# RLC_renonant.net
KiCad netlist of a schematic drawn in Altium Designer
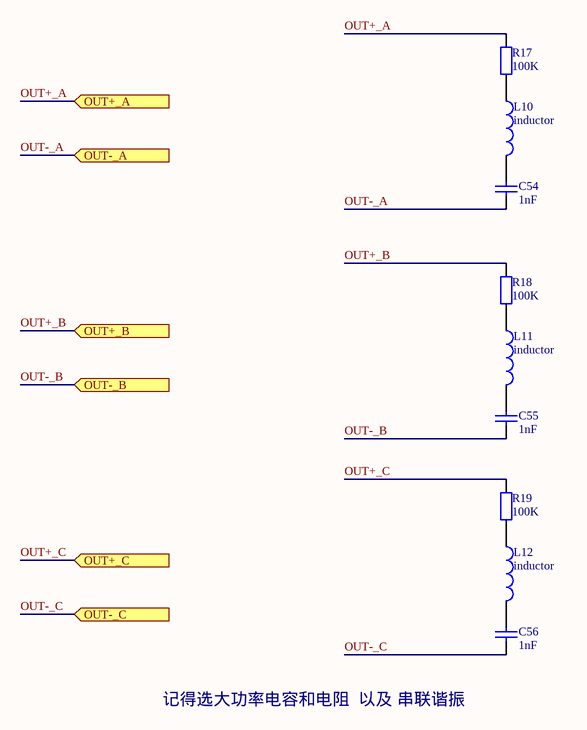
[diagram p0: RLC_renonant.SchDoc]

(export (version "E")
  (design (tool "Eeschema 10.0.6"))
  (components
    (comp (ref "C54") (value "1nF") (footprint "RAD-0.2") (libsource (lib "MyLibrary") (part "Cap")))
    (comp (ref "C55") (value "1nF") (footprint "RAD-0.2") (libsource (lib "MyLibrary") (part "Cap")))
    (comp (ref "C56") (value "1nF") (footprint "RAD-0.2") (libsource (lib "MyLibrary") (part "Cap")))
    (comp (ref "L10") (value "inductor") (footprint "inductor") (libsource (lib "Dugu") (part "inductor")))
    (comp (ref "L11") (value "inductor") (footprint "inductor") (libsource (lib "Dugu") (part "inductor")))
    (comp (ref "L12") (value "inductor") (footprint "inductor") (libsource (lib "Dugu") (part "inductor")))
    (comp (ref "R17")
      (value "100K")
      (footprint "Res_big")
      (fields
        (field (name "Comment") "Res")
        (field (name "原理图绘制者") "刘永钦")
        (field (name "原理图提供者") "刘永钦")
        (field (name "原理图审核人1") "徐鹏飞")
        (field (name "封装0805绘制者") "刘永钦")
        (field (name "封装0805提供者") "刘永钦")
        (field (name "封装0805审核人1") "徐鹏飞")
        (field (name "原理图审核人2") "朱觉文")
        (field (name "封装0805审核人2") "朱觉文")
        (field (name "封装0603提供者") "刘永钦")
        (field (name "封装0603审核人2") "朱觉文")
        (field (name "封装0603审核人1") "徐鹏飞")
        (field (name "封装2512-RESC6332X06N审核人2") "朱觉文")
        (field (name "封装2512-RESC6332X06N提供者") "刘永钦")
        (field (name "封装2512-RESC6332X06N审核人1") "徐鹏飞")
        (field (name "封装0603绘制者") "刘永钦")
        (field (name "封装2512-RESC6332X06N绘制者") "刘永钦")
      )
      (libsource (lib "DuGu") (part "Res"))
    )
    (comp (ref "R18")
      (value "100K")
      (footprint "Res_big")
      (fields
        (field (name "Comment") "Res")
        (field (name "原理图绘制者") "刘永钦")
        (field (name "原理图提供者") "刘永钦")
        (field (name "原理图审核人1") "徐鹏飞")
        (field (name "封装0805绘制者") "刘永钦")
        (field (name "封装0805提供者") "刘永钦")
        (field (name "封装0805审核人1") "徐鹏飞")
        (field (name "原理图审核人2") "朱觉文")
        (field (name "封装0805审核人2") "朱觉文")
        (field (name "封装0603提供者") "刘永钦")
        (field (name "封装0603审核人2") "朱觉文")
        (field (name "封装0603审核人1") "徐鹏飞")
        (field (name "封装2512-RESC6332X06N审核人2") "朱觉文")
        (field (name "封装2512-RESC6332X06N提供者") "刘永钦")
        (field (name "封装2512-RESC6332X06N审核人1") "徐鹏飞")
        (field (name "封装0603绘制者") "刘永钦")
        (field (name "封装2512-RESC6332X06N绘制者") "刘永钦")
      )
      (libsource (lib "DuGu") (part "Res"))
    )
    (comp (ref "R19")
      (value "100K")
      (footprint "Res_big")
      (fields
        (field (name "Comment") "Res")
        (field (name "原理图绘制者") "刘永钦")
        (field (name "原理图提供者") "刘永钦")
        (field (name "原理图审核人1") "徐鹏飞")
        (field (name "封装0805绘制者") "刘永钦")
        (field (name "封装0805提供者") "刘永钦")
        (field (name "封装0805审核人1") "徐鹏飞")
        (field (name "原理图审核人2") "朱觉文")
        (field (name "封装0805审核人2") "朱觉文")
        (field (name "封装0603提供者") "刘永钦")
        (field (name "封装0603审核人2") "朱觉文")
        (field (name "封装0603审核人1") "徐鹏飞")
        (field (name "封装2512-RESC6332X06N审核人2") "朱觉文")
        (field (name "封装2512-RESC6332X06N提供者") "刘永钦")
        (field (name "封装2512-RESC6332X06N审核人1") "徐鹏飞")
        (field (name "封装0603绘制者") "刘永钦")
        (field (name "封装2512-RESC6332X06N绘制者") "刘永钦")
      )
      (libsource (lib "DuGu") (part "Res"))
    )
  )
  (nets
    (net (code "1") (name "/OUT+_A") (class "Default")
      (node (ref "R17") (pin "1") (pinfunction "1_1") (pintype "passive"))
    )
    (net (code "2") (name "/OUT+_B") (class "Default")
      (node (ref "R18") (pin "1") (pinfunction "1_1") (pintype "passive"))
    )
    (net (code "3") (name "/OUT+_C") (class "Default")
      (node (ref "R19") (pin "1") (pinfunction "1_1") (pintype "passive"))
    )
    (net (code "4") (name "/OUT-_A") (class "Default")
      (node (ref "C54") (pin "1") (pinfunction "1_1") (pintype "passive"))
    )
    (net (code "5") (name "/OUT-_B") (class "Default")
      (node (ref "C55") (pin "1") (pinfunction "1_1") (pintype "passive"))
    )
    (net (code "6") (name "/OUT-_C") (class "Default")
      (node (ref "C56") (pin "1") (pinfunction "1_1") (pintype "passive"))
    )
    (net (code "7") (name "Net-(C54-Pad2)") (class "Default")
      (node (ref "C54") (pin "2") (pinfunction "2_2") (pintype "passive"))
      (node (ref "L10") (pin "2") (pinfunction "2_2") (pintype "passive"))
    )
    (net (code "8") (name "Net-(C55-Pad2)") (class "Default")
      (node (ref "C55") (pin "2") (pinfunction "2_2") (pintype "passive"))
      (node (ref "L11") (pin "2") (pinfunction "2_2") (pintype "passive"))
    )
    (net (code "9") (name "Net-(C56-Pad2)") (class "Default")
      (node (ref "C56") (pin "2") (pinfunction "2_2") (pintype "passive"))
      (node (ref "L12") (pin "2") (pinfunction "2_2") (pintype "passive"))
    )
    (net (code "10") (name "Net-(L10-Pad1)") (class "Default")
      (node (ref "L10") (pin "1") (pinfunction "1_1") (pintype "passive"))
      (node (ref "R17") (pin "2") (pinfunction "2_2") (pintype "passive"))
    )
    (net (code "11") (name "Net-(L11-Pad1)") (class "Default")
      (node (ref "L11") (pin "1") (pinfunction "1_1") (pintype "passive"))
      (node (ref "R18") (pin "2") (pinfunction "2_2") (pintype "passive"))
    )
    (net (code "12") (name "Net-(L12-Pad1)") (class "Default")
      (node (ref "L12") (pin "1") (pinfunction "1_1") (pintype "passive"))
      (node (ref "R19") (pin "2") (pinfunction "2_2") (pintype "passive"))
    )
  )
)
